# Mutteruhr.net
KiCad netlist of a schematic drawn in EAGLE
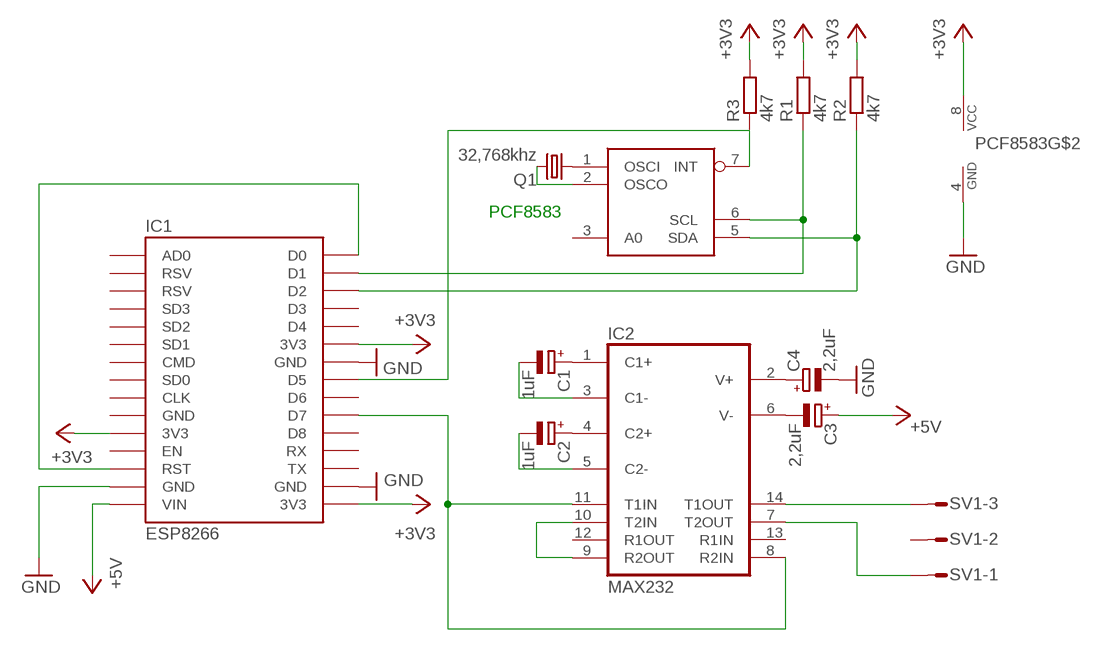
[diagram p0: schematic, sheet 1]

(export (version "E")
  (design (tool "Eeschema 10.0.6"))
  (components
    (comp (ref "C1")
      (value "1uF")
      (footprint "eagle-import:E2,5-5")
      (libsource (lib "eagle-import") (part "CPOL-EUE2.5-5"))
    )
    (comp (ref "C2")
      (value "1uF")
      (footprint "eagle-import:E2,5-5")
      (libsource (lib "eagle-import") (part "CPOL-EUE2.5-5"))
    )
    (comp (ref "C3")
      (value "2,2uF")
      (footprint "eagle-import:E2,5-5")
      (libsource (lib "eagle-import") (part "CPOL-EUE2.5-5"))
    )
    (comp (ref "C4")
      (value "2,2uF")
      (footprint "eagle-import:E2,5-5")
      (libsource (lib "eagle-import") (part "CPOL-EUE2.5-5"))
    )
    (comp (ref "IC1")
      (value "ESP8266")
      (footprint "eagle-import:ESP12E_DEVKIT")
      (libsource (lib "eagle-import") (part "ESP12E_DEVKIT"))
    )
    (comp (ref "IC2")
      (value "MAX232")
      (footprint "eagle-import:DIL16")
      (fields (field (name "MF") "MAXIM") (field (name "MPN") "MAX232ACPE+"))
      (libsource (lib "eagle-import") (part "MAX232"))
    )
    (comp (ref "PCF8583")
      (value "PCF8583P")
      (footprint "eagle-import:DIL08")
      (libsource (lib "eagle-import") (part "PCF8583P"))
    )
    (comp (ref "Q1")
      (value "32,768khz")
      (footprint "eagle-import:TC38H")
      (libsource (lib "eagle-import") (part "CRYSTALTC38H"))
    )
    (comp (ref "R1")
      (value "4k7")
      (footprint "eagle-import:0207_10")
      (libsource (lib "eagle-import") (part "R-EU_0207/10"))
    )
    (comp (ref "R2")
      (value "4k7")
      (footprint "eagle-import:0207_10")
      (libsource (lib "eagle-import") (part "R-EU_0207/10"))
    )
    (comp (ref "R3")
      (value "4k7")
      (footprint "eagle-import:0207_10")
      (libsource (lib "eagle-import") (part "R-EU_0207/10"))
    )
    (comp (ref "SV1")
      (value "MT6-3")
      (footprint "eagle-import:MT6-3")
      (libsource (lib "eagle-import") (part "MT6-3"))
    )
  )
  (nets
    (net (code "1") (name "+3V3") (class "Default")
      (node (ref "IC1") (pin "3V3@0") (pinfunction "3V3_3V3@0") (pintype "bidirectional"))
      (node (ref "IC1") (pin "3V3@1") (pinfunction "3V3_3V3@1") (pintype "bidirectional"))
      (node (ref "IC1") (pin "3V3@2") (pinfunction "3V3_3V3@2") (pintype "bidirectional"))
      (node (ref "PCF8583") (pin "8") (pinfunction "VCC_8") (pintype "power_in"))
      (node (ref "R1") (pin "2") (pinfunction "2_2") (pintype "passive"))
      (node (ref "R2") (pin "2") (pinfunction "2_2") (pintype "passive"))
      (node (ref "R3") (pin "2") (pinfunction "2_2") (pintype "passive"))
    )
    (net (code "2") (name "+5V") (class "Default")
      (node (ref "C3") (pin "+") (pinfunction "+_+") (pintype "passive"))
      (node (ref "IC1") (pin "VIN") (pinfunction "VIN_VIN") (pintype "bidirectional"))
    )
    (net (code "3") (name "GND") (class "Default")
      (node (ref "C4") (pin "-") (pinfunction "-_-") (pintype "passive"))
      (node (ref "IC1") (pin "GND@1") (pinfunction "GND_GND@1") (pintype "bidirectional"))
      (node (ref "IC1") (pin "GND@2") (pinfunction "GND_GND@2") (pintype "bidirectional"))
      (node (ref "IC1") (pin "GND@3") (pinfunction "GND_GND@3") (pintype "bidirectional"))
      (node (ref "PCF8583") (pin "4") (pinfunction "GND_4") (pintype "power_in"))
    )
    (net (code "4") (name "Net-(IC1-PadD0)") (class "Default")
      (node (ref "IC1") (pin "D0") (pinfunction "D0_D0") (pintype "bidirectional"))
      (node (ref "IC1") (pin "RST") (pinfunction "RST_RST") (pintype "bidirectional"))
    )
    (net (code "5") (name "Net-(IC2A-C1+)") (class "Default")
      (node (ref "C1") (pin "+") (pinfunction "+_+") (pintype "passive"))
      (node (ref "IC2") (pin "1") (pinfunction "C1+_1") (pintype "bidirectional"))
    )
    (net (code "6") (name "Net-(IC2A-C1-)") (class "Default")
      (node (ref "C1") (pin "-") (pinfunction "-_-") (pintype "passive"))
      (node (ref "IC2") (pin "3") (pinfunction "C1-_3") (pintype "bidirectional"))
    )
    (net (code "7") (name "Net-(IC2A-C2+)") (class "Default")
      (node (ref "C2") (pin "+") (pinfunction "+_+") (pintype "passive"))
      (node (ref "IC2") (pin "4") (pinfunction "C2+_4") (pintype "bidirectional"))
    )
    (net (code "8") (name "Net-(IC2A-C2-)") (class "Default")
      (node (ref "C2") (pin "-") (pinfunction "-_-") (pintype "passive"))
      (node (ref "IC2") (pin "5") (pinfunction "C2-_5") (pintype "bidirectional"))
    )
    (net (code "9") (name "Net-(IC2A-R2IN)") (class "Default")
      (node (ref "IC1") (pin "D7") (pinfunction "D7_D7") (pintype "bidirectional"))
      (node (ref "IC2") (pin "11") (pinfunction "T1IN_11") (pintype "input"))
      (node (ref "IC2") (pin "8") (pinfunction "R2IN_8") (pintype "input"))
    )
    (net (code "10") (name "Net-(IC2A-R2OUT)") (class "Default")
      (node (ref "IC2") (pin "10") (pinfunction "T2IN_10") (pintype "input"))
      (node (ref "IC2") (pin "9") (pinfunction "R2OUT_9") (pintype "output"))
    )
    (net (code "11") (name "Net-(IC2A-T1OUT)") (class "Default")
      (node (ref "IC2") (pin "14") (pinfunction "T1OUT_14") (pintype "output"))
      (node (ref "SV1") (pin "3") (pinfunction "S_3") (pintype "passive"))
    )
    (net (code "12") (name "Net-(IC2A-T2OUT)") (class "Default")
      (node (ref "IC2") (pin "7") (pinfunction "T2OUT_7") (pintype "output"))
      (node (ref "SV1") (pin "1") (pinfunction "S_1") (pintype "passive"))
    )
    (net (code "13") (name "Net-(IC2A-V+)") (class "Default")
      (node (ref "C4") (pin "+") (pinfunction "+_+") (pintype "passive"))
      (node (ref "IC2") (pin "2") (pinfunction "V+_2") (pintype "bidirectional"))
    )
    (net (code "14") (name "Net-(IC2A-V-)") (class "Default")
      (node (ref "C3") (pin "-") (pinfunction "-_-") (pintype "passive"))
      (node (ref "IC2") (pin "6") (pinfunction "V-_6") (pintype "bidirectional"))
    )
    (net (code "15") (name "Net-(PCF8583A-INT)") (class "Default")
      (node (ref "IC1") (pin "D5") (pinfunction "D5_D5") (pintype "bidirectional"))
      (node (ref "PCF8583") (pin "7") (pinfunction "INT_7") (pintype "output"))
      (node (ref "R3") (pin "1") (pinfunction "1_1") (pintype "passive"))
    )
    (net (code "16") (name "Net-(PCF8583A-OSCI)") (class "Default")
      (node (ref "PCF8583") (pin "1") (pinfunction "OSCI_1") (pintype "input"))
      (node (ref "Q1") (pin "1") (pinfunction "1_1") (pintype "passive"))
    )
    (net (code "17") (name "Net-(PCF8583A-OSCO)") (class "Default")
      (node (ref "PCF8583") (pin "2") (pinfunction "OSCO_2") (pintype "output"))
      (node (ref "Q1") (pin "2") (pinfunction "2_2") (pintype "passive"))
    )
    (net (code "18") (name "Net-(PCF8583A-SCL)") (class "Default")
      (node (ref "IC1") (pin "D1") (pinfunction "D1_D1") (pintype "bidirectional"))
      (node (ref "PCF8583") (pin "6") (pinfunction "SCL_6") (pintype "input"))
      (node (ref "R1") (pin "1") (pinfunction "1_1") (pintype "passive"))
    )
    (net (code "19") (name "Net-(PCF8583A-SDA)") (class "Default")
      (node (ref "IC1") (pin "D2") (pinfunction "D2_D2") (pintype "bidirectional"))
      (node (ref "PCF8583") (pin "5") (pinfunction "SDA_5") (pintype "bidirectional"))
      (node (ref "R2") (pin "1") (pinfunction "1_1") (pintype "passive"))
    )
    (net (code "20") (name "unconnected-(IC1-GND-PadGND@0)") (class "Default")
      (node (ref "IC1") (pin "GND@0") (pinfunction "GND_GND@0") (pintype "bidirectional"))
    )
    (net (code "21") (name "unconnected-(IC1-PadAD0)") (class "Default")
      (node (ref "IC1") (pin "AD0") (pinfunction "AD0_AD0") (pintype "bidirectional"))
    )
    (net (code "22") (name "unconnected-(IC1-PadCLK)") (class "Default")
      (node (ref "IC1") (pin "CLK") (pinfunction "CLK_CLK") (pintype "bidirectional"))
    )
    (net (code "23") (name "unconnected-(IC1-PadCMD)") (class "Default")
      (node (ref "IC1") (pin "CMD") (pinfunction "CMD_CMD") (pintype "bidirectional"))
    )
    (net (code "24") (name "unconnected-(IC1-PadD3)") (class "Default")
      (node (ref "IC1") (pin "D3") (pinfunction "D3_D3") (pintype "bidirectional"))
    )
    (net (code "25") (name "unconnected-(IC1-PadD4)") (class "Default")
      (node (ref "IC1") (pin "D4") (pinfunction "D4_D4") (pintype "bidirectional"))
    )
    (net (code "26") (name "unconnected-(IC1-PadD6)") (class "Default")
      (node (ref "IC1") (pin "D6") (pinfunction "D6_D6") (pintype "bidirectional"))
    )
    (net (code "27") (name "unconnected-(IC1-PadD8)") (class "Default")
      (node (ref "IC1") (pin "D8") (pinfunction "D8_D8") (pintype "bidirectional"))
    )
    (net (code "28") (name "unconnected-(IC1-PadEN)") (class "Default")
      (node (ref "IC1") (pin "EN") (pinfunction "EN_EN") (pintype "bidirectional"))
    )
    (net (code "29") (name "unconnected-(IC1-PadRX)") (class "Default")
      (node (ref "IC1") (pin "RX") (pinfunction "RX_RX") (pintype "bidirectional"))
    )
    (net (code "30") (name "unconnected-(IC1-PadSD0)") (class "Default")
      (node (ref "IC1") (pin "SD0") (pinfunction "SD0_SD0") (pintype "bidirectional"))
    )
    (net (code "31") (name "unconnected-(IC1-PadSD1)") (class "Default")
      (node (ref "IC1") (pin "SD1") (pinfunction "SD1_SD1") (pintype "bidirectional"))
    )
    (net (code "32") (name "unconnected-(IC1-PadSD2)") (class "Default")
      (node (ref "IC1") (pin "SD2") (pinfunction "SD2_SD2") (pintype "bidirectional"))
    )
    (net (code "33") (name "unconnected-(IC1-PadSD3)") (class "Default")
      (node (ref "IC1") (pin "SD3") (pinfunction "SD3_SD3") (pintype "bidirectional"))
    )
    (net (code "34") (name "unconnected-(IC1-PadTX)") (class "Default")
      (node (ref "IC1") (pin "TX") (pinfunction "TX_TX") (pintype "bidirectional"))
    )
    (net (code "35") (name "unconnected-(IC1-RSV-PadRSV@0)") (class "Default")
      (node (ref "IC1") (pin "RSV@0") (pinfunction "RSV_RSV@0") (pintype "bidirectional"))
    )
    (net (code "36") (name "unconnected-(IC1-RSV-PadRSV@1)") (class "Default")
      (node (ref "IC1") (pin "RSV@1") (pinfunction "RSV_RSV@1") (pintype "bidirectional"))
    )
    (net (code "37") (name "unconnected-(IC2A-R1IN-Pad13)") (class "Default")
      (node (ref "IC2") (pin "13") (pinfunction "R1IN_13") (pintype "input"))
    )
    (net (code "38") (name "unconnected-(IC2A-R1OUT-Pad12)") (class "Default")
      (node (ref "IC2") (pin "12") (pinfunction "R1OUT_12") (pintype "output"))
    )
    (net (code "39") (name "unconnected-(PCF8583A-A0-Pad3)") (class "Default")
      (node (ref "PCF8583") (pin "3") (pinfunction "A0_3") (pintype "input"))
    )
    (net (code "40") (name "unconnected-(SV1B-S-Pad2)") (class "Default")
      (node (ref "SV1") (pin "2") (pinfunction "S_2") (pintype "passive"))
    )
  )
)
